# NN23_Dual_Src_Optode_00.net
KiCad netlist of a schematic drawn in EAGLE
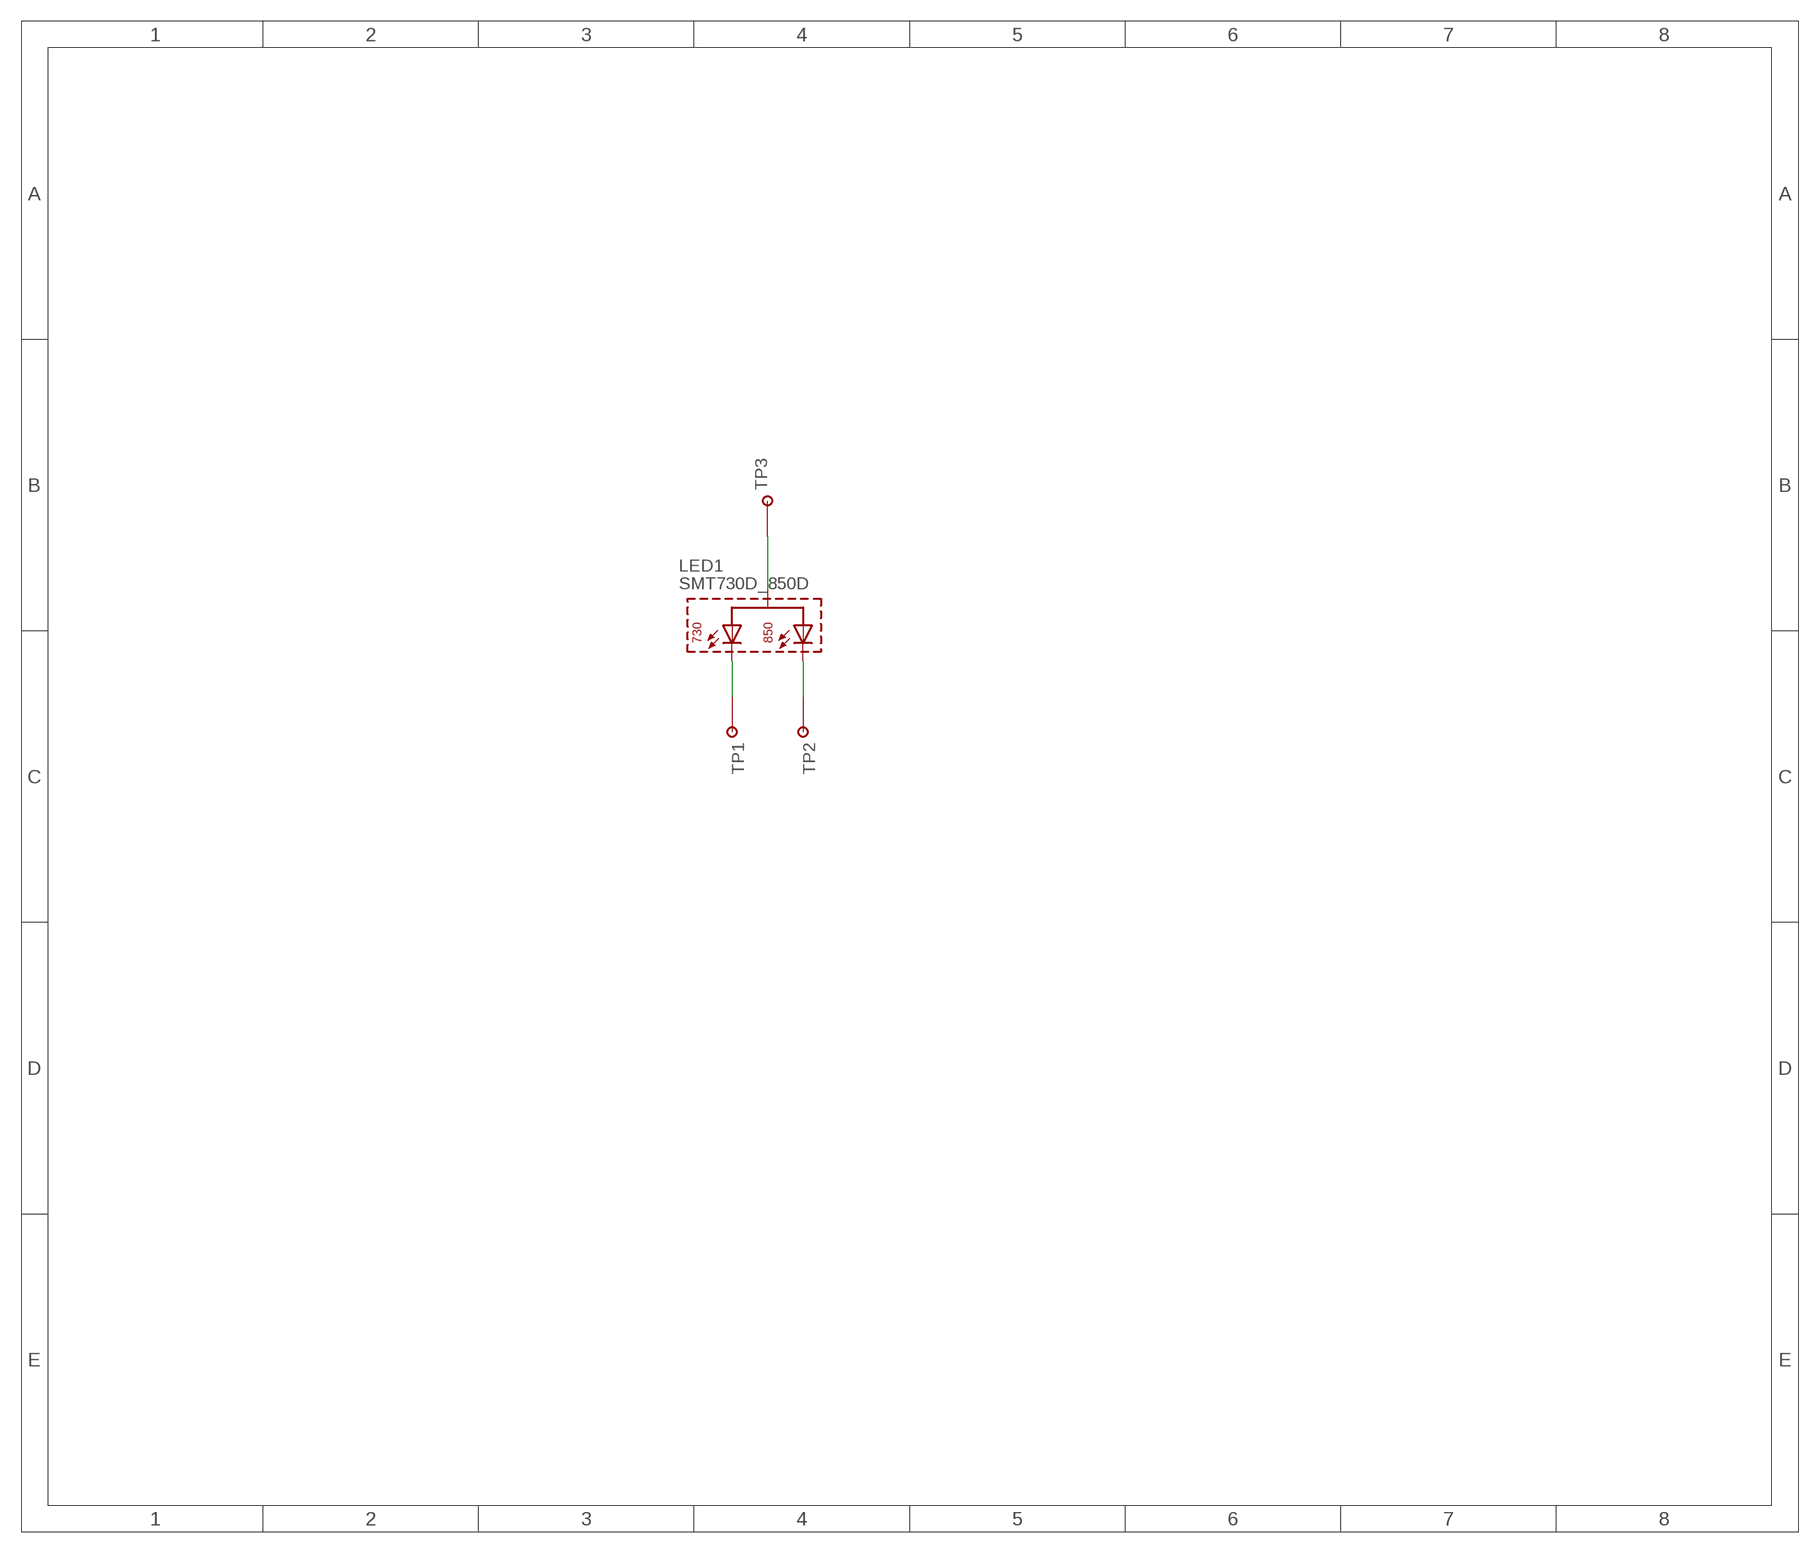
[diagram p0: schematic, sheet 1]

(export (version "E")
  (design (tool "Eeschema 10.0.6"))
  (components
    (comp (ref "LED1")
      (value "SMT730D_850D")
      (footprint "eagle-import:SMT730D_850D")
      (libsource (lib "eagle-import") (part "SMT730D_850D"))
    )
    (comp (ref "TP1")
      (value "TESTPOINT_PADMEDIUM")
      (footprint "eagle-import:TESTPAD_MEDIUM")
      (libsource (lib "eagle-import") (part "TESTPOINT_PADMEDIUM"))
    )
    (comp (ref "TP2")
      (value "TESTPOINT_PADMEDIUM")
      (footprint "eagle-import:TESTPAD_MEDIUM")
      (libsource (lib "eagle-import") (part "TESTPOINT_PADMEDIUM"))
    )
    (comp (ref "TP3")
      (value "TESTPOINT_PADMEDIUM")
      (footprint "eagle-import:TESTPAD_MEDIUM")
      (libsource (lib "eagle-import") (part "TESTPOINT_PADMEDIUM"))
    )
  )
  (nets
    (net (code "1") (name "Net-(LED1-PadA)") (class "Default")
      (node (ref "LED1") (pin "A") (pinfunction "A_A") (pintype "passive"))
      (node (ref "TP3") (pin "P$1") (pinfunction "P$1_P$1") (pintype "bidirectional"))
    )
    (net (code "2") (name "Net-(LED1-PadC7)") (class "Default")
      (node (ref "LED1") (pin "C7") (pinfunction "C7_C7") (pintype "passive"))
      (node (ref "TP1") (pin "P$1") (pinfunction "P$1_P$1") (pintype "bidirectional"))
    )
    (net (code "3") (name "Net-(LED1-PadC8)") (class "Default")
      (node (ref "LED1") (pin "C8") (pinfunction "C8_C8") (pintype "passive"))
      (node (ref "TP2") (pin "P$1") (pinfunction "P$1_P$1") (pintype "bidirectional"))
    )
  )
)
